# rectifier.net
KiCad netlist of a schematic drawn in Altium Designer
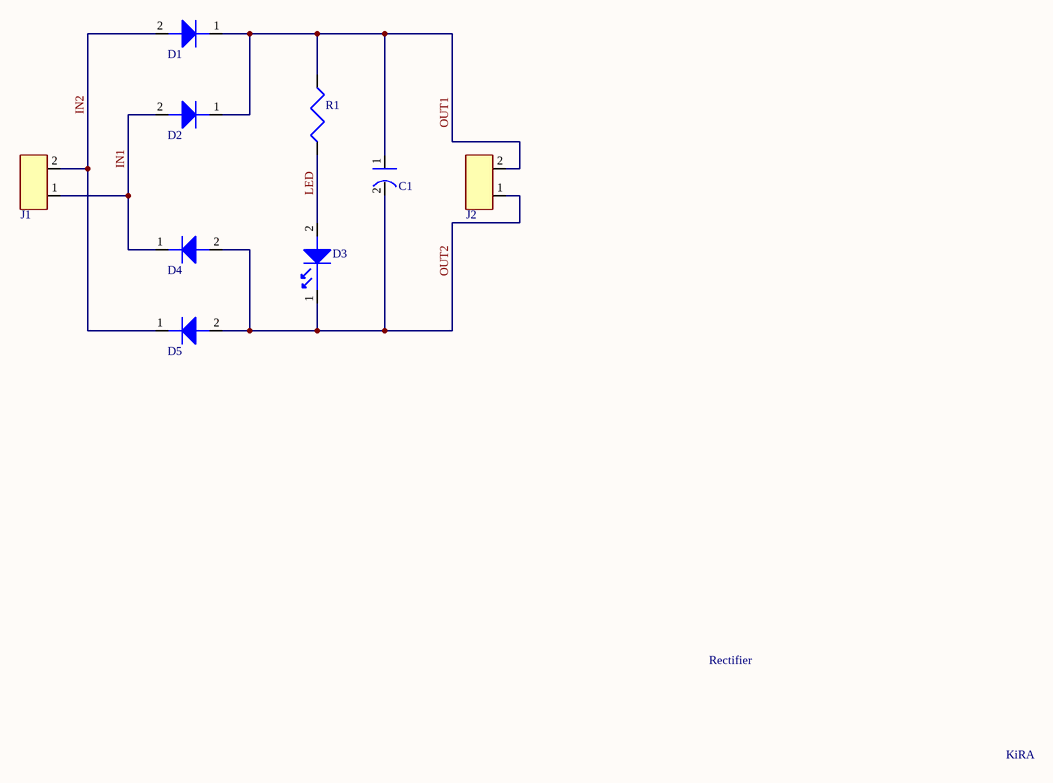
[diagram p0: rectifier.SchDoc]

(export (version "E")
  (design (tool "Eeschema 10.0.6"))
  (components
    (comp (ref "C1")
      (value "Capacitor 1000uF 25V")
      (footprint "Capacitor 1000uF 25V")
      (fields
        (field (name "MANUFACTURER") "CKR/CKS")
        (field (name "PART NO") "108CKR025M")
        (field (name "VOLTAGE") "25V")
      )
      (libsource (lib "rectifier_Schlib1") (part "108CKR025M"))
    )
    (comp (ref "D1")
      (value "Diode")
      (footprint "Diode 1N914")
      (fields (field (name "MANUFACTURER") "onsemi") (field (name "PART NO") "1N914"))
      (libsource (lib "rectifier_Schlib1") (part "1N914"))
    )
    (comp (ref "D2")
      (value "Diode")
      (footprint "Diode 1N914")
      (fields (field (name "MANUFACTURER") "onsemi") (field (name "PART NO") "1N914"))
      (libsource (lib "rectifier_Schlib1") (part "1N914"))
    )
    (comp (ref "D3")
      (value "3mm red LED")
      (footprint "LED 3mm red")
      (fields (field (name "MANUFACTURER") "TT electronics") (field (name "PART NO") "OVLBR4CL"))
      (libsource (lib "rectifier_Schlib1") (part "OVLBR4CL"))
    )
    (comp (ref "D4")
      (value "Diode")
      (footprint "Diode 1N914")
      (fields (field (name "MANUFACTURER") "onsemi") (field (name "PART NO") "1N914"))
      (libsource (lib "rectifier_Schlib1") (part "1N914"))
    )
    (comp (ref "D5")
      (value "Diode")
      (footprint "Diode 1N914")
      (fields (field (name "MANUFACTURER") "onsemi") (field (name "PART NO") "1N914"))
      (libsource (lib "rectifier_Schlib1") (part "1N914"))
    )
    (comp (ref "J1")
      (value "1X2 header, screw")
      (footprint "Header, Screw")
      (description "header, Screw, PCB mount")
      (fields (field (name "MANUFACTURER") "TE Connectivity") (field (name "PART NO") "796683-2"))
      (libsource (lib "rectifier_Schlib1") (part "796683-2"))
    )
    (comp (ref "J2")
      (value "1X2 header, screw")
      (footprint "Header, Screw")
      (description "header, Screw, PCB mount")
      (fields (field (name "MANUFACTURER") "TE Connectivity") (field (name "PART NO") "796683-2"))
      (libsource (lib "rectifier_Schlib1") (part "796683-2"))
    )
    (comp (ref "R1")
      (value "10K, 0.25W")
      (footprint "Resistor 10K, 0.25W")
      (fields (field (name "MANUFACTURER") "Yageo Corporation"))
      (libsource (lib "rectifier_Schlib1") (part "Resistor"))
    )
  )
  (nets
    (net (code "1") (name "/IN1") (class "Default")
      (node (ref "D2") (pin "2") (pinfunction "2_2") (pintype "passive"))
      (node (ref "D4") (pin "1") (pinfunction "1_1") (pintype "passive"))
      (node (ref "J1") (pin "1") (pinfunction "1_1") (pintype "passive"))
    )
    (net (code "2") (name "/IN2") (class "Default")
      (node (ref "D1") (pin "2") (pinfunction "2_2") (pintype "passive"))
      (node (ref "D5") (pin "1") (pinfunction "1_1") (pintype "passive"))
      (node (ref "J1") (pin "2") (pinfunction "2_2") (pintype "passive"))
    )
    (net (code "3") (name "/LED") (class "Default")
      (node (ref "D3") (pin "2") (pinfunction "2_2") (pintype "passive"))
      (node (ref "R1") (pin "1") (pinfunction "1_1") (pintype "passive"))
    )
    (net (code "4") (name "/OUT1") (class "Default")
      (node (ref "C1") (pin "1") (pinfunction "1_1") (pintype "passive"))
      (node (ref "D1") (pin "1") (pinfunction "1_1") (pintype "passive"))
      (node (ref "D2") (pin "1") (pinfunction "1_1") (pintype "passive"))
      (node (ref "J2") (pin "2") (pinfunction "2_2") (pintype "passive"))
      (node (ref "R1") (pin "2") (pinfunction "2_2") (pintype "passive"))
    )
    (net (code "5") (name "/OUT2") (class "Default")
      (node (ref "C1") (pin "2") (pinfunction "2_2") (pintype "passive"))
      (node (ref "D3") (pin "1") (pinfunction "1_1") (pintype "passive"))
      (node (ref "D4") (pin "2") (pinfunction "2_2") (pintype "passive"))
      (node (ref "D5") (pin "2") (pinfunction "2_2") (pintype "passive"))
      (node (ref "J2") (pin "1") (pinfunction "1_1") (pintype "passive"))
    )
  )
)
